# 03_-_Majority_Trigger.net
KiCad netlist of a schematic drawn in Altium Designer
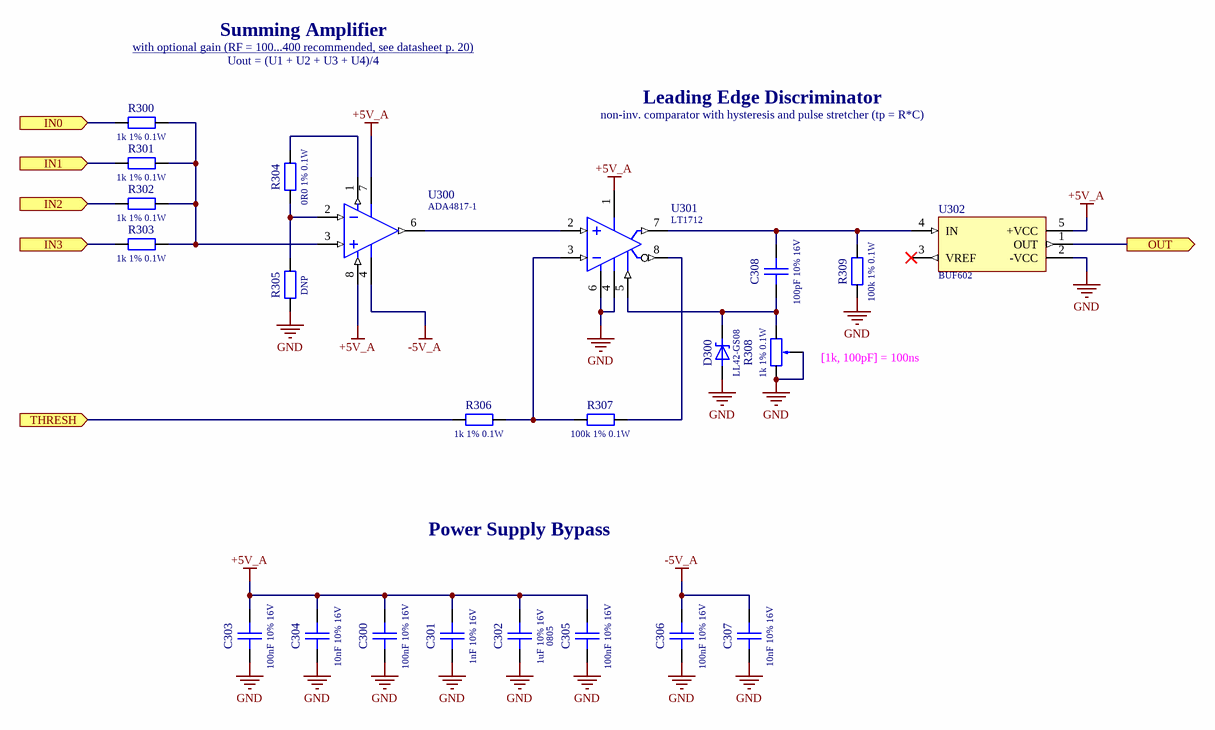
[diagram p0: [03] - Majority Trigger.SchDoc]

(export (version "E")
  (design (tool "Eeschema 10.0.6"))
  (components
    (comp (ref "C300")
      (value "100nF 10% 16V")
      (footprint "0603_CAP")
      (description "Simple generic capacitor.")
      (libsource (lib "CustomComponents") (part "Capacitor"))
    )
    (comp (ref "C301")
      (value "1nF 10% 16V")
      (footprint "0603_CAP")
      (description "Simple generic capacitor.")
      (libsource (lib "CustomComponents") (part "Capacitor"))
    )
    (comp (ref "C302")
      (value "1uF 10% 16V")
      (footprint "0805_CAP")
      (description "Simple generic capacitor.")
      (fields (field (name "PACKAGEREFERENCE") "0805"))
      (libsource (lib "CustomComponents") (part "Capacitor"))
    )
    (comp (ref "C303")
      (value "100nF 10% 16V")
      (footprint "0603_CAP")
      (description "Simple generic capacitor.")
      (libsource (lib "CustomComponents") (part "Capacitor"))
    )
    (comp (ref "C304")
      (value "10nF 10% 16V")
      (footprint "0603_CAP")
      (description "Simple generic capacitor.")
      (libsource (lib "CustomComponents") (part "Capacitor"))
    )
    (comp (ref "C305")
      (value "100nF 10% 16V")
      (footprint "0603_CAP")
      (description "Simple generic capacitor.")
      (libsource (lib "CustomComponents") (part "Capacitor"))
    )
    (comp (ref "C306")
      (value "100nF 10% 16V")
      (footprint "0603_CAP")
      (description "Simple generic capacitor.")
      (libsource (lib "CustomComponents") (part "Capacitor"))
    )
    (comp (ref "C307")
      (value "10nF 10% 16V")
      (footprint "0603_CAP")
      (description "Simple generic capacitor.")
      (libsource (lib "CustomComponents") (part "Capacitor"))
    )
    (comp (ref "C308")
      (value "100pF 10% 16V")
      (footprint "0603_CAP")
      (description "Simple generic capacitor.")
      (libsource (lib "CustomComponents") (part "Capacitor"))
    )
    (comp (ref "D300")
      (value "LL42-GS08")
      (footprint "MiniMELF")
      (description "Simple schottky diode.")
      (fields (field (name "MANUFACTURER") "Vishay"))
      (libsource (lib "CustomComponents") (part "Schottky Diode"))
    )
    (comp (ref "R300")
      (value "1k 1% 0.1W")
      (footprint "0603_RES")
      (description "Simple generic resistor.")
      (libsource (lib "CustomComponents") (part "Resistor"))
    )
    (comp (ref "R301")
      (value "1k 1% 0.1W")
      (footprint "0603_RES")
      (description "Simple generic resistor.")
      (libsource (lib "CustomComponents") (part "Resistor"))
    )
    (comp (ref "R302")
      (value "1k 1% 0.1W")
      (footprint "0603_RES")
      (description "Simple generic resistor.")
      (libsource (lib "CustomComponents") (part "Resistor"))
    )
    (comp (ref "R303")
      (value "1k 1% 0.1W")
      (footprint "0603_RES")
      (description "Simple generic resistor.")
      (libsource (lib "CustomComponents") (part "Resistor"))
    )
    (comp (ref "R304")
      (value "0R0 1% 0.1W")
      (footprint "0603_RES")
      (description "Simple generic resistor.")
      (libsource (lib "CustomComponents") (part "Resistor"))
    )
    (comp (ref "R305")
      (value "DNP")
      (footprint "0603_RES")
      (description "Simple generic resistor.")
      (libsource (lib "CustomComponents") (part "Resistor"))
    )
    (comp (ref "R306")
      (value "1k 1% 0.1W")
      (footprint "0603_RES")
      (description "Simple generic resistor.")
      (libsource (lib "CustomComponents") (part "Resistor"))
    )
    (comp (ref "R307")
      (value "100k 1% 0.1W")
      (footprint "0603_RES")
      (description "Simple generic resistor.")
      (libsource (lib "CustomComponents") (part "Resistor"))
    )
    (comp (ref "R308")
      (value "1k 1% 0.1W")
      (footprint "3224W")
      (description "Simple generic potentiometer.")
      (libsource (lib "CustomComponents") (part "Potentiometer"))
    )
    (comp (ref "R309")
      (value "100k 1% 0.1W")
      (footprint "0603_RES")
      (description "Simple generic resistor.")
      (libsource (lib "CustomComponents") (part "Resistor"))
    )
    (comp (ref "U300")
      (value "ADA4817-1")
      (footprint "SOIC_8")
      (description "Low Noise, 1 GHz FastFET Op Amps")
      (fields (field (name "MANUFACTURER") "Analog Devices"))
      (libsource (lib "CustomComponents") (part "ADA4817-1"))
    )
    (comp (ref "U301")
      (value "LT1712")
      (footprint "MSOP-8")
      (description "Single/Dual 4.5ns, 3V/5V/±5V, Rail-to-Rail Comparators")
      (fields (field (name "MANUFACTURER") "Analog Devices") (field (name "PARTNUMBER") "LT1712CGN"))
      (libsource (lib "CustomComponents") (part "LT1712"))
    )
    (comp (ref "U302")
      (value "BUF602")
      (footprint "SOT-23-5")
      (description "High-Speed, Closed-Loop Buffer.")
      (fields (field (name "MANUFACTURER") "Texas Instruments") (field (name "PARTNUMBER") "BUF602IDBVT"))
      (libsource (lib "CustomComponents") (part "BUF602"))
    )
  )
  (nets
    (net (code "1") (name "+5V_A") (class "Default")
      (node (ref "C300") (pin "2") (pinfunction "2_2") (pintype "passive"))
      (node (ref "C301") (pin "2") (pinfunction "2_2") (pintype "passive"))
      (node (ref "C302") (pin "2") (pinfunction "2_2") (pintype "passive"))
      (node (ref "C303") (pin "2") (pinfunction "2_2") (pintype "passive"))
      (node (ref "C304") (pin "2") (pinfunction "2_2") (pintype "passive"))
      (node (ref "C305") (pin "2") (pinfunction "2_2") (pintype "passive"))
      (node (ref "U300") (pin "7") (pinfunction "+VS_7") (pintype "power_in"))
      (node (ref "U300") (pin "8") (pinfunction "~{PD}_8") (pintype "input"))
      (node (ref "U301") (pin "1") (pinfunction "+V_1") (pintype "power_in"))
      (node (ref "U302") (pin "5") (pinfunction "+VCC_5") (pintype "power_in"))
    )
    (net (code "2") (name "-5V_A") (class "Default")
      (node (ref "C306") (pin "2") (pinfunction "2_2") (pintype "passive"))
      (node (ref "C307") (pin "2") (pinfunction "2_2") (pintype "passive"))
      (node (ref "U300") (pin "4") (pinfunction "-VS_4") (pintype "power_in"))
    )
    (net (code "3") (name "/IN0") (class "Default")
      (node (ref "R300") (pin "2") (pinfunction "2_2") (pintype "passive"))
    )
    (net (code "4") (name "/IN1") (class "Default")
      (node (ref "R301") (pin "2") (pinfunction "2_2") (pintype "passive"))
    )
    (net (code "5") (name "/IN2") (class "Default")
      (node (ref "R302") (pin "2") (pinfunction "2_2") (pintype "passive"))
    )
    (net (code "6") (name "/IN3") (class "Default")
      (node (ref "R303") (pin "2") (pinfunction "2_2") (pintype "passive"))
    )
    (net (code "7") (name "/OUT") (class "Default")
      (node (ref "U302") (pin "1") (pinfunction "OUT_1") (pintype "output"))
    )
    (net (code "8") (name "/THRESH") (class "Default")
      (node (ref "R306") (pin "2") (pinfunction "2_2") (pintype "passive"))
    )
    (net (code "9") (name "GND") (class "Default")
      (node (ref "C300") (pin "1") (pinfunction "1_1") (pintype "passive"))
      (node (ref "C301") (pin "1") (pinfunction "1_1") (pintype "passive"))
      (node (ref "C302") (pin "1") (pinfunction "1_1") (pintype "passive"))
      (node (ref "C303") (pin "1") (pinfunction "1_1") (pintype "passive"))
      (node (ref "C304") (pin "1") (pinfunction "1_1") (pintype "passive"))
      (node (ref "C305") (pin "1") (pinfunction "1_1") (pintype "passive"))
      (node (ref "C306") (pin "1") (pinfunction "1_1") (pintype "passive"))
      (node (ref "C307") (pin "1") (pinfunction "1_1") (pintype "passive"))
      (node (ref "D300") (pin "2") (pinfunction "A_2") (pintype "passive"))
      (node (ref "R305") (pin "2") (pinfunction "2_2") (pintype "passive"))
      (node (ref "R308") (pin "1") (pinfunction "CCW_1") (pintype "passive"))
      (node (ref "R308") (pin "2") (pinfunction "WIPER_2") (pintype "passive"))
      (node (ref "R309") (pin "2") (pinfunction "2_2") (pintype "passive"))
      (node (ref "U301") (pin "4") (pinfunction "-V_4") (pintype "power_in"))
      (node (ref "U301") (pin "6") (pinfunction "GND_6") (pintype "power_in"))
      (node (ref "U302") (pin "2") (pinfunction "-VCC_2") (pintype "power_in"))
    )
    (net (code "10") (name "Net-(D300-K)") (class "Default")
      (node (ref "C308") (pin "1") (pinfunction "1_1") (pintype "passive"))
      (node (ref "D300") (pin "1") (pinfunction "K_1") (pintype "passive"))
      (node (ref "R308") (pin "3") (pinfunction "CW_3") (pintype "passive"))
      (node (ref "U301") (pin "5") (pinfunction "LE_5") (pintype "input"))
    )
    (net (code "11") (name "Net-(U300-FB)") (class "Default")
      (node (ref "R304") (pin "1") (pinfunction "1_1") (pintype "passive"))
      (node (ref "U300") (pin "1") (pinfunction "FB_1") (pintype "output"))
    )
    (net (code "12") (name "Net-(U300-IN+)") (class "Default")
      (node (ref "R300") (pin "1") (pinfunction "1_1") (pintype "passive"))
      (node (ref "R301") (pin "1") (pinfunction "1_1") (pintype "passive"))
      (node (ref "R302") (pin "1") (pinfunction "1_1") (pintype "passive"))
      (node (ref "R303") (pin "1") (pinfunction "1_1") (pintype "passive"))
      (node (ref "U300") (pin "3") (pinfunction "IN+_3") (pintype "input"))
    )
    (net (code "13") (name "Net-(U300-IN-)") (class "Default")
      (node (ref "R304") (pin "2") (pinfunction "2_2") (pintype "passive"))
      (node (ref "R305") (pin "1") (pinfunction "1_1") (pintype "passive"))
      (node (ref "U300") (pin "2") (pinfunction "IN-_2") (pintype "input"))
    )
    (net (code "14") (name "Net-(U300-OUT)") (class "Default")
      (node (ref "U300") (pin "6") (pinfunction "OUT_6") (pintype "output"))
      (node (ref "U301") (pin "2") (pinfunction "+IN_2") (pintype "input"))
    )
    (net (code "15") (name "Net-(U301--IN)") (class "Default")
      (node (ref "R306") (pin "1") (pinfunction "1_1") (pintype "passive"))
      (node (ref "R307") (pin "2") (pinfunction "2_2") (pintype "passive"))
      (node (ref "U301") (pin "3") (pinfunction "-IN_3") (pintype "input"))
    )
    (net (code "16") (name "Net-(U301-Q)") (class "Default")
      (node (ref "C308") (pin "2") (pinfunction "2_2") (pintype "passive"))
      (node (ref "R309") (pin "1") (pinfunction "1_1") (pintype "passive"))
      (node (ref "U301") (pin "7") (pinfunction "Q_7") (pintype "output"))
      (node (ref "U302") (pin "4") (pinfunction "IN_4") (pintype "input"))
    )
    (net (code "17") (name "Net-(U301-~{Q})") (class "Default")
      (node (ref "R307") (pin "1") (pinfunction "1_1") (pintype "passive"))
      (node (ref "U301") (pin "8") (pinfunction "~{Q}_8") (pintype "output"))
    )
    (net (code "18") (name "unconnected-(U302-VREF-Pad3)") (class "Default")
      (node (ref "U302") (pin "3") (pinfunction "VREF_3") (pintype "output+no_connect"))
    )
  )
)
